# 4-Power.net
KiCad netlist of a schematic drawn in Altium Designer
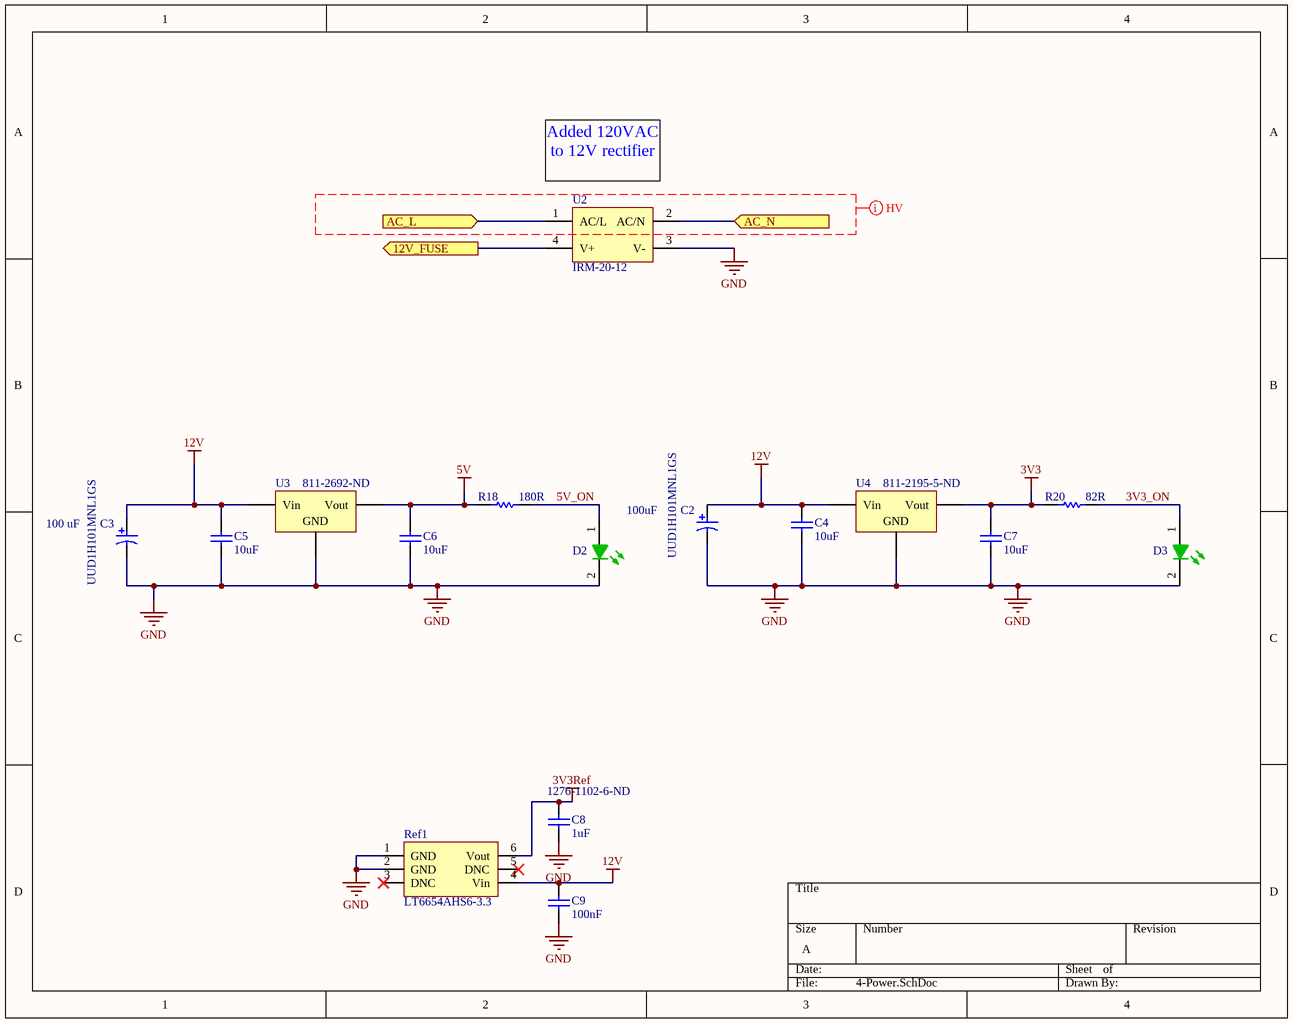
[diagram p0: 4-Power.SchDoc]

(export (version "E")
  (design (tool "Eeschema 10.0.6"))
  (components
    (comp (ref "C2")
      (value "UUD1H101MNL1GS")
      (footprint "NIC-CAPA2-8X10_V")
      (fields (field (name "MANUFACTURER") "Nichicon") (field (name "TOLERANCE") "±20%"))
      (libsource (lib "Altium Content Vault") (part "CMP-0687-00073-1"))
    )
    (comp (ref "C3")
      (value "UUD1H101MNL1GS")
      (footprint "NIC-CAPA2-8X10_V")
      (fields
        (field (name "MANUFACTURER") "Nichicon")
        (field (name "RATED CAPACITANCE") "100 uF")
        (field (name "TOLERANCE") "±20%")
      )
      (libsource (lib "Altium Content Vault") (part "CMP-0687-00073-1"))
    )
    (comp (ref "C4")
      (value "10uF")
      (footprint "C1210_M")
      (description "Capacitor")
      (fields
        (field (name "MANUFACTURER") "Yageo")
        (field (name "MANUFACTURER PART NUMBER") "CC1210ZKY5V8BB106")
      )
      (libsource (lib "Miscellaneous Devices") (part "Cap"))
    )
    (comp (ref "C5")
      (value "10uF")
      (footprint "C1210_M")
      (description "Capacitor")
      (fields
        (field (name "MANUFACTURER") "Yageo")
        (field (name "MANUFACTURER PART NUMBER") "CC1210ZKY5V8BB106")
      )
      (libsource (lib "Miscellaneous Devices") (part "Cap"))
    )
    (comp (ref "C6")
      (value "10uF")
      (footprint "C1210_M")
      (description "Capacitor")
      (fields
        (field (name "MANUFACTURER") "Yageo")
        (field (name "MANUFACTURER PART NUMBER") "CC1210ZKY5V8BB106")
      )
      (libsource (lib "Miscellaneous Devices") (part "Cap"))
    )
    (comp (ref "C7")
      (value "10uF")
      (footprint "C1210_M")
      (description "Capacitor")
      (fields
        (field (name "MANUFACTURER") "Yageo")
        (field (name "MANUFACTURER PART NUMBER") "CC1210ZKY5V8BB106")
      )
      (libsource (lib "Miscellaneous Devices") (part "Cap"))
    )
    (comp (ref "C8")
      (value "1uF")
      (footprint "1608[0603]")
      (description "Capacitor")
      (fields
        (field (name "MANUFACTURER") "Murata Electronics North America")
        (field (name "MANUFACTURER PART NUMBER") "GRM188R61E105KA12D")
        (field (name "SUPPLIER PART NUMBER 1") "1276-1102-6-ND")
      )
      (libsource (lib "Miscellaneous Devices") (part "Cap"))
    )
    (comp (ref "C9")
      (value "100nF")
      (footprint "1608[0603]")
      (description "Capacitor")
      (fields
        (field (name "MANUFACTURER") "Yageo")
        (field (name "MANUFACTURER PART NUMBER") "CC0603KRX7R9BB104")
      )
      (libsource (lib "Miscellaneous Devices") (part "Cap"))
    )
    (comp (ref "D2")
      (value "KP-1608MGC")
      (footprint "KING-0603LED_GREEN_V")
      (description "LED, SMT, 0603(1608), 1.1mm thickness, Green")
      (fields (field (name "MANUFACTURER") "Kingbright"))
      (libsource (lib "Altium Content Vault") (part "KING-LED-GREEN-A1K2-2"))
    )
    (comp (ref "D3")
      (value "KP-1608MGC")
      (footprint "KING-0603LED_GREEN_V")
      (description "LED, SMT, 0603(1608), 1.1mm thickness, Green")
      (fields (field (name "MANUFACTURER") "Kingbright"))
      (libsource (lib "Altium Content Vault") (part "KING-LED-GREEN-A1K2-2"))
    )
    (comp (ref "R18")
      (value "180R")
      (footprint "1608[0603]")
      (description "Resistor")
      (fields
        (field (name "MANUFACTURER") "Yageo")
        (field (name "MANUFACTURER PART NUMBER") "RC0603JR-07180RL")
      )
      (libsource (lib "Miscellaneous Devices") (part "Res1"))
    )
    (comp (ref "R20")
      (value "82R")
      (footprint "1608[0603]")
      (description "Resistor")
      (fields
        (field (name "MANUFACTURER") "Yageo")
        (field (name "MANUFACTURER PART NUMBER") "RC0603JR-0782RL")
      )
      (libsource (lib "Miscellaneous Devices") (part "Res1"))
    )
    (comp (ref "Ref1")
      (value "LT6654AHS6-3.3")
      (footprint "TSOT-23")
      (description "TSOT-23-56")
      (fields
        (field (name "DIGIKEY PART NUMBER") "LT6654AHS6-3.3#TRMPBFCT-ND")
        (field (name "MANUFACTURER") "Linear Technology")
      )
      (libsource (lib "VCU Library") (part "LT6654AHS6-3.3"))
    )
    (comp (ref "U2")
      (value "IRM-20-12")
      (footprint "MEANW-IRM-20-12")
      (description "Single Output Encapsulated Type, 12 V, 1.8 A, 21.6 W, -40 to 85 degC, 4-Pin THD, RoHS")
      (fields (field (name "MANUFACTURER") "Mean Well"))
      (libsource (lib "Altium Content Vault") (part "MEANW-IRM-20-12-4"))
    )
    (comp (ref "U3")
      (value "Volt Reg")
      (footprint "DCDC_HORIZONTAL")
      (description "Voltage Regulator")
      (fields
        (field (name "SUPPLIER PART NUMBER 1") "811-2692-ND")
        (field (name "PUBLISHER") "Altium Limited")
      )
      (libsource (lib "Miscellaneous Devices") (part "Volt Reg"))
    )
    (comp (ref "U4")
      (value "Volt Reg")
      (footprint "DCDC_VERTICAL")
      (description "Voltage Regulator")
      (fields
        (field (name "SUPPLIER PART NUMBER 1") "811-2195-5-ND")
        (field (name "PUBLISHER") "Altium Limited")
      )
      (libsource (lib "Miscellaneous Devices") (part "Volt Reg"))
    )
  )
  (nets
    (net (code "1") (name "/3V3_ON") (class "Default")
      (node (ref "D3") (pin "1") (pinfunction "A_1") (pintype "passive"))
      (node (ref "R20") (pin "2") (pinfunction "2_2") (pintype "passive"))
    )
    (net (code "2") (name "/5V_ON") (class "Default")
      (node (ref "D2") (pin "1") (pinfunction "A_1") (pintype "passive"))
      (node (ref "R18") (pin "2") (pinfunction "2_2") (pintype "passive"))
    )
    (net (code "3") (name "/12V_FUSE") (class "Default")
      (node (ref "U2") (pin "4") (pinfunction "V+_4") (pintype "power_in"))
    )
    (net (code "4") (name "/AC_L") (class "Default")
      (node (ref "U2") (pin "1") (pinfunction "AC/L_1") (pintype "passive"))
    )
    (net (code "5") (name "/AC_N") (class "Default")
      (node (ref "U2") (pin "2") (pinfunction "AC/N_2") (pintype "passive"))
    )
    (net (code "6") (name "3V3") (class "Default")
      (node (ref "C7") (pin "2") (pinfunction "2_2") (pintype "passive"))
      (node (ref "R20") (pin "1") (pinfunction "1_1") (pintype "passive"))
      (node (ref "U4") (pin "3") (pinfunction "Vout_3") (pintype "passive"))
    )
    (net (code "7") (name "3V3Ref") (class "Default")
      (node (ref "C8") (pin "2") (pinfunction "2_2") (pintype "passive"))
      (node (ref "Ref1") (pin "6") (pinfunction "Vout_6") (pintype "passive"))
    )
    (net (code "8") (name "5V") (class "Default")
      (node (ref "C6") (pin "2") (pinfunction "2_2") (pintype "passive"))
      (node (ref "R18") (pin "1") (pinfunction "1_1") (pintype "passive"))
      (node (ref "U3") (pin "3") (pinfunction "Vout_3") (pintype "passive"))
    )
    (net (code "9") (name "12V") (class "Default")
      (node (ref "C2") (pin "1") (pinfunction "1_1") (pintype "passive"))
      (node (ref "C3") (pin "1") (pinfunction "1_1") (pintype "passive"))
      (node (ref "C4") (pin "2") (pinfunction "2_2") (pintype "passive"))
      (node (ref "C5") (pin "2") (pinfunction "2_2") (pintype "passive"))
      (node (ref "C9") (pin "2") (pinfunction "2_2") (pintype "passive"))
      (node (ref "Ref1") (pin "4") (pinfunction "Vin_4") (pintype "passive"))
      (node (ref "U3") (pin "1") (pinfunction "Vin_1") (pintype "passive"))
      (node (ref "U4") (pin "1") (pinfunction "Vin_1") (pintype "passive"))
    )
    (net (code "10") (name "GND") (class "Default")
      (node (ref "C2") (pin "2") (pinfunction "2_2") (pintype "passive"))
      (node (ref "C3") (pin "2") (pinfunction "2_2") (pintype "passive"))
      (node (ref "C4") (pin "1") (pinfunction "1_1") (pintype "passive"))
      (node (ref "C5") (pin "1") (pinfunction "1_1") (pintype "passive"))
      (node (ref "C6") (pin "1") (pinfunction "1_1") (pintype "passive"))
      (node (ref "C7") (pin "1") (pinfunction "1_1") (pintype "passive"))
      (node (ref "C8") (pin "1") (pinfunction "1_1") (pintype "passive"))
      (node (ref "C9") (pin "1") (pinfunction "1_1") (pintype "passive"))
      (node (ref "D2") (pin "2") (pinfunction "K_2") (pintype "passive"))
      (node (ref "D3") (pin "2") (pinfunction "K_2") (pintype "passive"))
      (node (ref "Ref1") (pin "1") (pinfunction "GND_1") (pintype "passive"))
      (node (ref "Ref1") (pin "2") (pinfunction "GND_2") (pintype "passive"))
      (node (ref "U2") (pin "3") (pinfunction "V-_3") (pintype "power_in"))
      (node (ref "U3") (pin "2") (pinfunction "GND_2") (pintype "passive"))
      (node (ref "U4") (pin "2") (pinfunction "GND_2") (pintype "passive"))
    )
    (net (code "11") (name "unconnected-(Ref1-DNC-Pad3)") (class "Default")
      (node (ref "Ref1") (pin "3") (pinfunction "DNC_3") (pintype "passive+no_connect"))
    )
    (net (code "12") (name "unconnected-(Ref1-DNC-Pad5)") (class "Default")
      (node (ref "Ref1") (pin "5") (pinfunction "DNC_5") (pintype "passive+no_connect"))
    )
  )
)
